# CleanIt.net
KiCad netlist of a schematic drawn in EAGLE
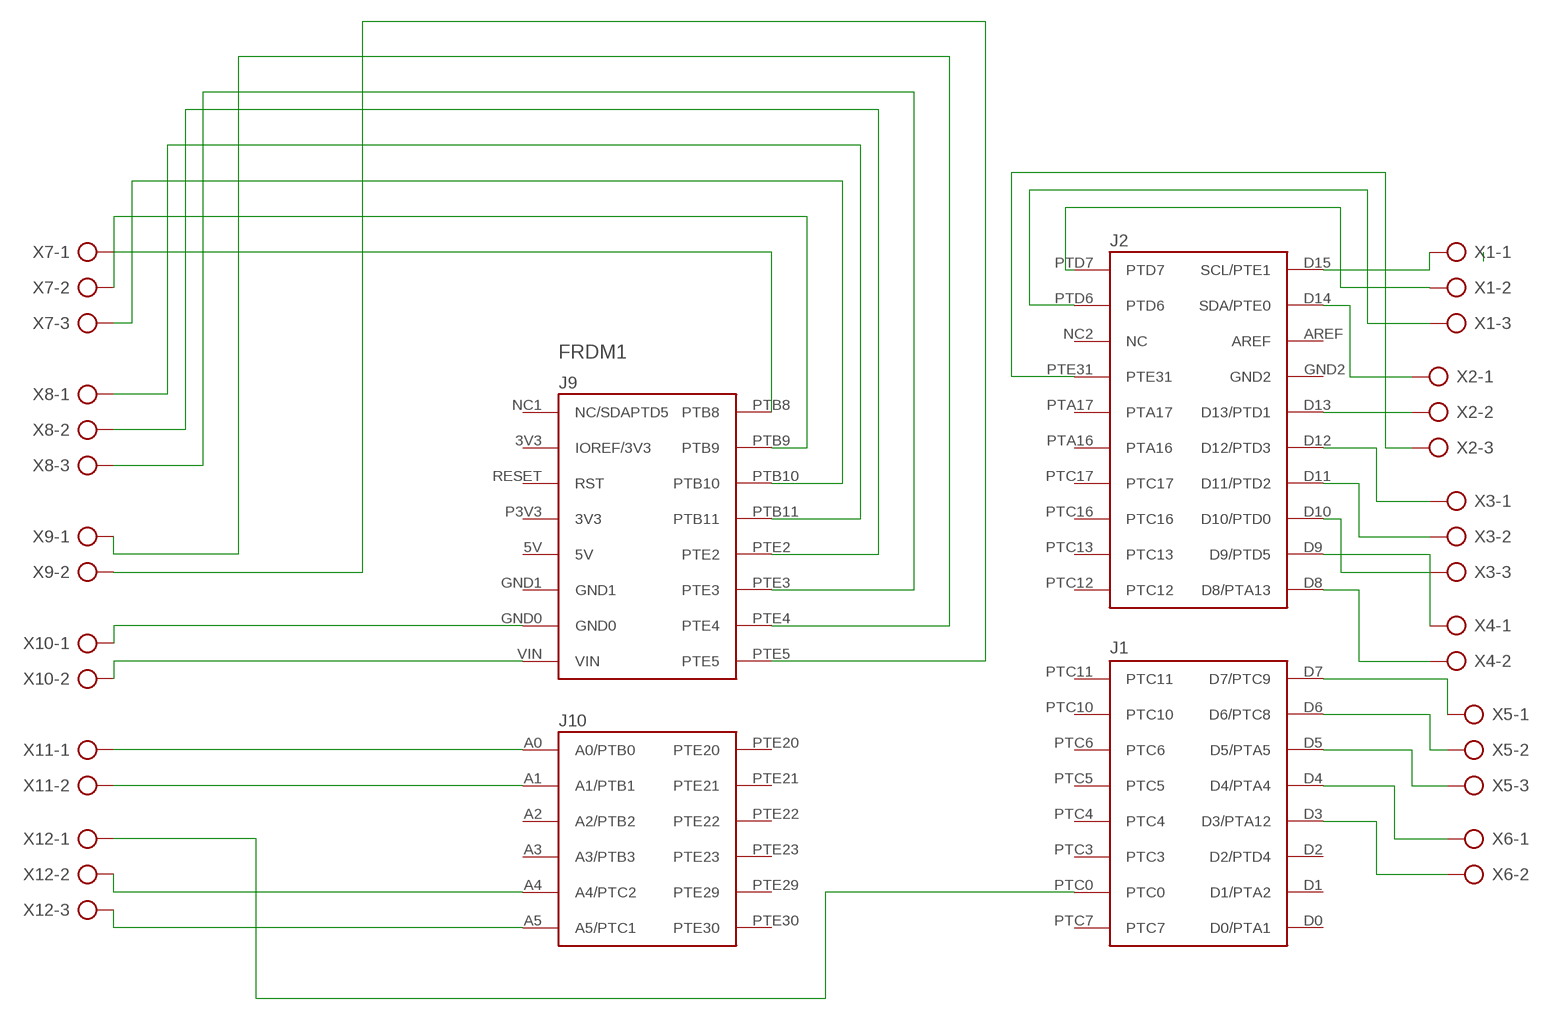
[diagram p0: schematic, sheet 1]

(export (version "E")
  (design (tool "Eeschema 10.0.6"))
  (components
    (comp (ref "FRDM1")
      (value "FRDM-KL25ZNORMAL")
      (footprint "eagle-import:FRDM_KL25Z_NORMAL")
      (fields (field (name "MF") "NXP USA") (field (name "MP") "FRDM-KL25Z"))
      (libsource (lib "eagle-import") (part "FRDM-KL25ZNORMAL"))
    )
    (comp (ref "X1")
      (value "AK500/3-H")
      (footprint "eagle-import:AK500_3-H")
      (libsource (lib "eagle-import") (part "AK500/3-H"))
    )
    (comp (ref "X2")
      (value "AK500/3-H")
      (footprint "eagle-import:AK500_3-H")
      (libsource (lib "eagle-import") (part "AK500/3-H"))
    )
    (comp (ref "X3")
      (value "AK500/3-H")
      (footprint "eagle-import:AK500_3-H")
      (libsource (lib "eagle-import") (part "AK500/3-H"))
    )
    (comp (ref "X4")
      (value "AK500/2-H")
      (footprint "eagle-import:AK500_2-H")
      (libsource (lib "eagle-import") (part "AK500/2-H"))
    )
    (comp (ref "X5")
      (value "AK500/3-H")
      (footprint "eagle-import:AK500_3-H")
      (libsource (lib "eagle-import") (part "AK500/3-H"))
    )
    (comp (ref "X6")
      (value "AK500/2-H")
      (footprint "eagle-import:AK500_2-H")
      (libsource (lib "eagle-import") (part "AK500/2-H"))
    )
    (comp (ref "X7")
      (value "AK500/3-H")
      (footprint "eagle-import:AK500_3-H")
      (libsource (lib "eagle-import") (part "AK500/3-H"))
    )
    (comp (ref "X8")
      (value "AK500/3-H")
      (footprint "eagle-import:AK500_3-H")
      (libsource (lib "eagle-import") (part "AK500/3-H"))
    )
    (comp (ref "X9")
      (value "AK500/2-H")
      (footprint "eagle-import:AK500_2-H")
      (libsource (lib "eagle-import") (part "AK500/2-H"))
    )
    (comp (ref "X10")
      (value "AK500/2-H")
      (footprint "eagle-import:AK500_2-H")
      (libsource (lib "eagle-import") (part "AK500/2-H"))
    )
    (comp (ref "X11")
      (value "AK500/2-H")
      (footprint "eagle-import:AK500_2-H")
      (libsource (lib "eagle-import") (part "AK500/2-H"))
    )
    (comp (ref "X12")
      (value "AK500/3-H")
      (footprint "eagle-import:AK500_3-H")
      (libsource (lib "eagle-import") (part "AK500/3-H"))
    )
  )
  (nets
    (net (code "1") (name "Net-(FRDM1-A0{slash}PTB0)") (class "Default")
      (node (ref "FRDM1") (pin "A0") (pinfunction "A0/PTB0_A0") (pintype "bidirectional"))
      (node (ref "X11") (pin "1") (pinfunction "KL_1") (pintype "passive"))
    )
    (net (code "2") (name "Net-(FRDM1-A1{slash}PTB1)") (class "Default")
      (node (ref "FRDM1") (pin "A1") (pinfunction "A1/PTB1_A1") (pintype "bidirectional"))
      (node (ref "X11") (pin "2") (pinfunction "KL_2") (pintype "passive"))
    )
    (net (code "3") (name "Net-(FRDM1-A4{slash}PTC2)") (class "Default")
      (node (ref "FRDM1") (pin "A4") (pinfunction "A4/PTC2_A4") (pintype "bidirectional"))
      (node (ref "X12") (pin "2") (pinfunction "KL_2") (pintype "passive"))
    )
    (net (code "4") (name "Net-(FRDM1-A5{slash}PTC1)") (class "Default")
      (node (ref "FRDM1") (pin "A5") (pinfunction "A5/PTC1_A5") (pintype "bidirectional"))
      (node (ref "X12") (pin "3") (pinfunction "KL_3") (pintype "passive"))
    )
    (net (code "5") (name "Net-(FRDM1-D3{slash}PTA12)") (class "Default")
      (node (ref "FRDM1") (pin "D3") (pinfunction "D3/PTA12_D3") (pintype "bidirectional"))
      (node (ref "X6") (pin "2") (pinfunction "KL_2") (pintype "passive"))
    )
    (net (code "6") (name "Net-(FRDM1-D4{slash}PTA4)") (class "Default")
      (node (ref "FRDM1") (pin "D4") (pinfunction "D4/PTA4_D4") (pintype "bidirectional"))
      (node (ref "X6") (pin "1") (pinfunction "KL_1") (pintype "passive"))
    )
    (net (code "7") (name "Net-(FRDM1-D5{slash}PTA5)") (class "Default")
      (node (ref "FRDM1") (pin "D5") (pinfunction "D5/PTA5_D5") (pintype "bidirectional"))
      (node (ref "X5") (pin "3") (pinfunction "KL_3") (pintype "passive"))
    )
    (net (code "8") (name "Net-(FRDM1-D6{slash}PTC8)") (class "Default")
      (node (ref "FRDM1") (pin "D6") (pinfunction "D6/PTC8_D6") (pintype "bidirectional"))
      (node (ref "X5") (pin "2") (pinfunction "KL_2") (pintype "passive"))
    )
    (net (code "9") (name "Net-(FRDM1-D7{slash}PTC9)") (class "Default")
      (node (ref "FRDM1") (pin "D7") (pinfunction "D7/PTC9_D7") (pintype "bidirectional"))
      (node (ref "X5") (pin "1") (pinfunction "KL_1") (pintype "passive"))
    )
    (net (code "10") (name "Net-(FRDM1-D8{slash}PTA13)") (class "Default")
      (node (ref "FRDM1") (pin "D8") (pinfunction "D8/PTA13_D8") (pintype "bidirectional"))
      (node (ref "X4") (pin "2") (pinfunction "KL_2") (pintype "passive"))
    )
    (net (code "11") (name "Net-(FRDM1-D9{slash}PTD5)") (class "Default")
      (node (ref "FRDM1") (pin "D9") (pinfunction "D9/PTD5_D9") (pintype "bidirectional"))
      (node (ref "X4") (pin "1") (pinfunction "KL_1") (pintype "passive"))
    )
    (net (code "12") (name "Net-(FRDM1-D10{slash}PTD0)") (class "Default")
      (node (ref "FRDM1") (pin "D10") (pinfunction "D10/PTD0_D10") (pintype "bidirectional"))
      (node (ref "X3") (pin "3") (pinfunction "KL_3") (pintype "passive"))
    )
    (net (code "13") (name "Net-(FRDM1-D11{slash}PTD2)") (class "Default")
      (node (ref "FRDM1") (pin "D11") (pinfunction "D11/PTD2_D11") (pintype "bidirectional"))
      (node (ref "X3") (pin "2") (pinfunction "KL_2") (pintype "passive"))
    )
    (net (code "14") (name "Net-(FRDM1-D12{slash}PTD3)") (class "Default")
      (node (ref "FRDM1") (pin "D12") (pinfunction "D12/PTD3_D12") (pintype "bidirectional"))
      (node (ref "X3") (pin "1") (pinfunction "KL_1") (pintype "passive"))
    )
    (net (code "15") (name "Net-(FRDM1-D13{slash}PTD1)") (class "Default")
      (node (ref "FRDM1") (pin "D13") (pinfunction "D13/PTD1_D13") (pintype "bidirectional"))
      (node (ref "X2") (pin "2") (pinfunction "KL_2") (pintype "passive"))
    )
    (net (code "16") (name "Net-(FRDM1-SCL{slash}PTE1)") (class "Default")
      (node (ref "FRDM1") (pin "D15") (pinfunction "SCL/PTE1_D15") (pintype "bidirectional"))
      (node (ref "X1") (pin "1") (pinfunction "KL_1") (pintype "passive"))
    )
    (net (code "17") (name "Net-(FRDM1-SDA{slash}PTE0)") (class "Default")
      (node (ref "FRDM1") (pin "D14") (pinfunction "SDA/PTE0_D14") (pintype "bidirectional"))
      (node (ref "X2") (pin "1") (pinfunction "KL_1") (pintype "passive"))
    )
    (net (code "18") (name "Net-(X1B-KL)") (class "Default")
      (node (ref "FRDM1") (pin "PTD7") (pinfunction "PTD7_PTD7") (pintype "bidirectional"))
      (node (ref "X1") (pin "2") (pinfunction "KL_2") (pintype "passive"))
    )
    (net (code "19") (name "Net-(X1C-KL)") (class "Default")
      (node (ref "FRDM1") (pin "PTD6") (pinfunction "PTD6_PTD6") (pintype "bidirectional"))
      (node (ref "X1") (pin "3") (pinfunction "KL_3") (pintype "passive"))
    )
    (net (code "20") (name "Net-(X2C-KL)") (class "Default")
      (node (ref "FRDM1") (pin "PTE31") (pinfunction "PTE31_PTE31") (pintype "bidirectional"))
      (node (ref "X2") (pin "3") (pinfunction "KL_3") (pintype "passive"))
    )
    (net (code "21") (name "Net-(X7A-KL)") (class "Default")
      (node (ref "FRDM1") (pin "PTB8") (pinfunction "PTB8_PTB8") (pintype "bidirectional"))
      (node (ref "X7") (pin "1") (pinfunction "KL_1") (pintype "passive"))
    )
    (net (code "22") (name "Net-(X7B-KL)") (class "Default")
      (node (ref "FRDM1") (pin "PTB9") (pinfunction "PTB9_PTB9") (pintype "bidirectional"))
      (node (ref "X7") (pin "2") (pinfunction "KL_2") (pintype "passive"))
    )
    (net (code "23") (name "Net-(X7C-KL)") (class "Default")
      (node (ref "FRDM1") (pin "PTB10") (pinfunction "PTB10_PTB10") (pintype "bidirectional"))
      (node (ref "X7") (pin "3") (pinfunction "KL_3") (pintype "passive"))
    )
    (net (code "24") (name "Net-(X8A-KL)") (class "Default")
      (node (ref "FRDM1") (pin "PTB11") (pinfunction "PTB11_PTB11") (pintype "bidirectional"))
      (node (ref "X8") (pin "1") (pinfunction "KL_1") (pintype "passive"))
    )
    (net (code "25") (name "Net-(X8B-KL)") (class "Default")
      (node (ref "FRDM1") (pin "PTE2") (pinfunction "PTE2_PTE2") (pintype "bidirectional"))
      (node (ref "X8") (pin "2") (pinfunction "KL_2") (pintype "passive"))
    )
    (net (code "26") (name "Net-(X8C-KL)") (class "Default")
      (node (ref "FRDM1") (pin "PTE3") (pinfunction "PTE3_PTE3") (pintype "bidirectional"))
      (node (ref "X8") (pin "3") (pinfunction "KL_3") (pintype "passive"))
    )
    (net (code "27") (name "Net-(X9A-KL)") (class "Default")
      (node (ref "FRDM1") (pin "PTE4") (pinfunction "PTE4_PTE4") (pintype "bidirectional"))
      (node (ref "X9") (pin "1") (pinfunction "KL_1") (pintype "passive"))
    )
    (net (code "28") (name "Net-(X9B-KL)") (class "Default")
      (node (ref "FRDM1") (pin "PTE5") (pinfunction "PTE5_PTE5") (pintype "bidirectional"))
      (node (ref "X9") (pin "2") (pinfunction "KL_2") (pintype "passive"))
    )
    (net (code "29") (name "Net-(X10A-KL)") (class "Default")
      (node (ref "FRDM1") (pin "GND0") (pinfunction "GND0_GND0") (pintype "bidirectional"))
      (node (ref "X10") (pin "1") (pinfunction "KL_1") (pintype "passive"))
    )
    (net (code "30") (name "Net-(X10B-KL)") (class "Default")
      (node (ref "FRDM1") (pin "VIN") (pinfunction "VIN_VIN") (pintype "bidirectional"))
      (node (ref "X10") (pin "2") (pinfunction "KL_2") (pintype "passive"))
    )
    (net (code "31") (name "Net-(X12A-KL)") (class "Default")
      (node (ref "FRDM1") (pin "PTC0") (pinfunction "PTC0_PTC0") (pintype "bidirectional"))
      (node (ref "X12") (pin "1") (pinfunction "KL_1") (pintype "passive"))
    )
    (net (code "32") (name "unconnected-(FRDM1-3V3-PadP3V3)") (class "Default")
      (node (ref "FRDM1") (pin "P3V3") (pinfunction "3V3_P3V3") (pintype "bidirectional"))
    )
    (net (code "33") (name "unconnected-(FRDM1-A2{slash}PTB2-PadA2)") (class "Default")
      (node (ref "FRDM1") (pin "A2") (pinfunction "A2/PTB2_A2") (pintype "bidirectional"))
    )
    (net (code "34") (name "unconnected-(FRDM1-A3{slash}PTB3-PadA3)") (class "Default")
      (node (ref "FRDM1") (pin "A3") (pinfunction "A3/PTB3_A3") (pintype "bidirectional"))
    )
    (net (code "35") (name "unconnected-(FRDM1-D0{slash}PTA1-PadD0)") (class "Default")
      (node (ref "FRDM1") (pin "D0") (pinfunction "D0/PTA1_D0") (pintype "bidirectional"))
    )
    (net (code "36") (name "unconnected-(FRDM1-D1{slash}PTA2-PadD1)") (class "Default")
      (node (ref "FRDM1") (pin "D1") (pinfunction "D1/PTA2_D1") (pintype "bidirectional"))
    )
    (net (code "37") (name "unconnected-(FRDM1-D2{slash}PTD4-PadD2)") (class "Default")
      (node (ref "FRDM1") (pin "D2") (pinfunction "D2/PTD4_D2") (pintype "bidirectional"))
    )
    (net (code "38") (name "unconnected-(FRDM1-IOREF{slash}3V3-Pad3V3)") (class "Default")
      (node (ref "FRDM1") (pin "3V3") (pinfunction "IOREF/3V3_3V3") (pintype "bidirectional"))
    )
    (net (code "39") (name "unconnected-(FRDM1-NC-PadNC2)") (class "Default")
      (node (ref "FRDM1") (pin "NC2") (pinfunction "NC_NC2") (pintype "bidirectional"))
    )
    (net (code "40") (name "unconnected-(FRDM1-NC{slash}SDAPTD5-PadNC1)") (class "Default")
      (node (ref "FRDM1") (pin "NC1") (pinfunction "NC/SDAPTD5_NC1") (pintype "bidirectional"))
    )
    (net (code "41") (name "unconnected-(FRDM1-Pad5V)") (class "Default")
      (node (ref "FRDM1") (pin "5V") (pinfunction "5V_5V") (pintype "bidirectional"))
    )
    (net (code "42") (name "unconnected-(FRDM1-PadAREF)") (class "Default")
      (node (ref "FRDM1") (pin "AREF") (pinfunction "AREF_AREF") (pintype "bidirectional"))
    )
    (net (code "43") (name "unconnected-(FRDM1-PadGND1)") (class "Default")
      (node (ref "FRDM1") (pin "GND1") (pinfunction "GND1_GND1") (pintype "bidirectional"))
    )
    (net (code "44") (name "unconnected-(FRDM1-PadGND2)") (class "Default")
      (node (ref "FRDM1") (pin "GND2") (pinfunction "GND2_GND2") (pintype "bidirectional"))
    )
    (net (code "45") (name "unconnected-(FRDM1-PadPTA16)") (class "Default")
      (node (ref "FRDM1") (pin "PTA16") (pinfunction "PTA16_PTA16") (pintype "bidirectional"))
    )
    (net (code "46") (name "unconnected-(FRDM1-PadPTA17)") (class "Default")
      (node (ref "FRDM1") (pin "PTA17") (pinfunction "PTA17_PTA17") (pintype "bidirectional"))
    )
    (net (code "47") (name "unconnected-(FRDM1-PadPTC3)") (class "Default")
      (node (ref "FRDM1") (pin "PTC3") (pinfunction "PTC3_PTC3") (pintype "bidirectional"))
    )
    (net (code "48") (name "unconnected-(FRDM1-PadPTC4)") (class "Default")
      (node (ref "FRDM1") (pin "PTC4") (pinfunction "PTC4_PTC4") (pintype "bidirectional"))
    )
    (net (code "49") (name "unconnected-(FRDM1-PadPTC5)") (class "Default")
      (node (ref "FRDM1") (pin "PTC5") (pinfunction "PTC5_PTC5") (pintype "bidirectional"))
    )
    (net (code "50") (name "unconnected-(FRDM1-PadPTC6)") (class "Default")
      (node (ref "FRDM1") (pin "PTC6") (pinfunction "PTC6_PTC6") (pintype "bidirectional"))
    )
    (net (code "51") (name "unconnected-(FRDM1-PadPTC7)") (class "Default")
      (node (ref "FRDM1") (pin "PTC7") (pinfunction "PTC7_PTC7") (pintype "bidirectional"))
    )
    (net (code "52") (name "unconnected-(FRDM1-PadPTC10)") (class "Default")
      (node (ref "FRDM1") (pin "PTC10") (pinfunction "PTC10_PTC10") (pintype "bidirectional"))
    )
    (net (code "53") (name "unconnected-(FRDM1-PadPTC11)") (class "Default")
      (node (ref "FRDM1") (pin "PTC11") (pinfunction "PTC11_PTC11") (pintype "bidirectional"))
    )
    (net (code "54") (name "unconnected-(FRDM1-PadPTC12)") (class "Default")
      (node (ref "FRDM1") (pin "PTC12") (pinfunction "PTC12_PTC12") (pintype "bidirectional"))
    )
    (net (code "55") (name "unconnected-(FRDM1-PadPTC13)") (class "Default")
      (node (ref "FRDM1") (pin "PTC13") (pinfunction "PTC13_PTC13") (pintype "bidirectional"))
    )
    (net (code "56") (name "unconnected-(FRDM1-PadPTC16)") (class "Default")
      (node (ref "FRDM1") (pin "PTC16") (pinfunction "PTC16_PTC16") (pintype "bidirectional"))
    )
    (net (code "57") (name "unconnected-(FRDM1-PadPTC17)") (class "Default")
      (node (ref "FRDM1") (pin "PTC17") (pinfunction "PTC17_PTC17") (pintype "bidirectional"))
    )
    (net (code "58") (name "unconnected-(FRDM1-PadPTE20)") (class "Default")
      (node (ref "FRDM1") (pin "PTE20") (pinfunction "PTE20_PTE20") (pintype "bidirectional"))
    )
    (net (code "59") (name "unconnected-(FRDM1-PadPTE21)") (class "Default")
      (node (ref "FRDM1") (pin "PTE21") (pinfunction "PTE21_PTE21") (pintype "bidirectional"))
    )
    (net (code "60") (name "unconnected-(FRDM1-PadPTE22)") (class "Default")
      (node (ref "FRDM1") (pin "PTE22") (pinfunction "PTE22_PTE22") (pintype "bidirectional"))
    )
    (net (code "61") (name "unconnected-(FRDM1-PadPTE23)") (class "Default")
      (node (ref "FRDM1") (pin "PTE23") (pinfunction "PTE23_PTE23") (pintype "bidirectional"))
    )
    (net (code "62") (name "unconnected-(FRDM1-PadPTE29)") (class "Default")
      (node (ref "FRDM1") (pin "PTE29") (pinfunction "PTE29_PTE29") (pintype "bidirectional"))
    )
    (net (code "63") (name "unconnected-(FRDM1-PadPTE30)") (class "Default")
      (node (ref "FRDM1") (pin "PTE30") (pinfunction "PTE30_PTE30") (pintype "bidirectional"))
    )
    (net (code "64") (name "unconnected-(FRDM1-RST-PadRESET)") (class "Default")
      (node (ref "FRDM1") (pin "RESET") (pinfunction "RST_RESET") (pintype "bidirectional"))
    )
  )
)
